# Sheet1.net
KiCad netlist of a schematic drawn in Altium Designer
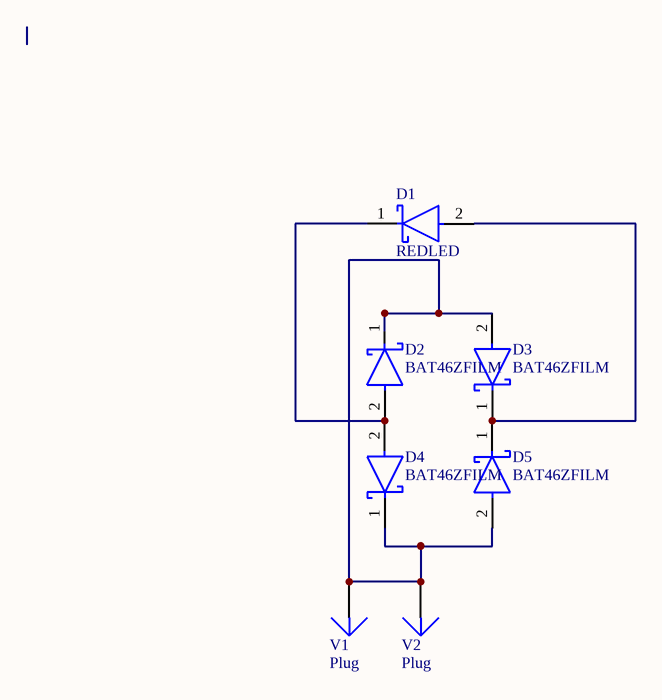
[diagram p0: Sheet1.SchDoc]

(export (version "E")
  (design (tool "Eeschema 10.0.6"))
  (components
    (comp (ref "D1")
      (value "REDLED")
      (footprint "FP-SOD-123-MFG")
      (description "DIODE SCHOTTKY 100V 150MA SOD123")
      (fields
        (field (name "MANUFACTURER") "STMicroelectronics")
        (field (name "MANUFACTURER PART NUMBER") "BAT46ZFILM")
      )
      (libsource (lib "Altium Content Vault") (part "1d6ec82d83fb6aee721767c19dac4b9"))
    )
    (comp (ref "D2")
      (value "BAT46ZFILM")
      (footprint "FP-SOD-123-MFG")
      (description "DIODE SCHOTTKY 100V 150MA SOD123")
      (fields
        (field (name "MANUFACTURER") "STMicroelectronics")
        (field (name "OCTOPART") "https://octopart.com/bat46zfilm-stmicroelectronics-658190")
      )
      (libsource (lib "Altium Content Vault") (part "1d6ec82d83fb6aee721767c19dac4b9"))
    )
    (comp (ref "D3")
      (value "BAT46ZFILM")
      (footprint "FP-SOD-123-MFG")
      (description "DIODE SCHOTTKY 100V 150MA SOD123")
      (fields
        (field (name "MANUFACTURER") "STMicroelectronics")
        (field (name "OCTOPART") "https://octopart.com/bat46zfilm-stmicroelectronics-658190")
      )
      (libsource (lib "Altium Content Vault") (part "1d6ec82d83fb6aee721767c19dac4b9"))
    )
    (comp (ref "D4")
      (value "BAT46ZFILM")
      (footprint "FP-SOD-123-MFG")
      (description "DIODE SCHOTTKY 100V 150MA SOD123")
      (fields
        (field (name "MANUFACTURER") "STMicroelectronics")
        (field (name "OCTOPART") "https://octopart.com/bat46zfilm-stmicroelectronics-658190")
      )
      (libsource (lib "Altium Content Vault") (part "1d6ec82d83fb6aee721767c19dac4b9"))
    )
    (comp (ref "D5")
      (value "BAT46ZFILM")
      (footprint "FP-SOD-123-MFG")
      (description "DIODE SCHOTTKY 100V 150MA SOD123")
      (fields
        (field (name "MANUFACTURER") "STMicroelectronics")
        (field (name "OCTOPART") "https://octopart.com/bat46zfilm-stmicroelectronics-658190")
      )
      (libsource (lib "Altium Content Vault") (part "1d6ec82d83fb6aee721767c19dac4b9"))
    )
    (comp (ref "V1")
      (value "Plug")
      (footprint "PIN1")
      (fields (field (name "PUBLISHER") "Altium Limited"))
      (libsource (lib "Miscellaneous Connectors") (part "Plug"))
    )
    (comp (ref "V2")
      (value "Plug")
      (footprint "PIN1")
      (fields (field (name "PUBLISHER") "Altium Limited"))
      (libsource (lib "Miscellaneous Connectors") (part "Plug"))
    )
  )
  (nets
    (net (code "1") (name "Net-(D1-A)") (class "Default")
      (node (ref "D1") (pin "2") (pinfunction "A_2") (pintype "passive"))
      (node (ref "D3") (pin "1") (pinfunction "C_1") (pintype "passive"))
      (node (ref "D5") (pin "1") (pinfunction "C_1") (pintype "passive"))
    )
    (net (code "2") (name "Net-(D1-C)") (class "Default")
      (node (ref "D1") (pin "1") (pinfunction "C_1") (pintype "passive"))
      (node (ref "D2") (pin "2") (pinfunction "A_2") (pintype "passive"))
      (node (ref "D4") (pin "2") (pinfunction "A_2") (pintype "passive"))
    )
    (net (code "3") (name "Net-(D2-C)") (class "Default")
      (node (ref "D2") (pin "1") (pinfunction "C_1") (pintype "passive"))
      (node (ref "D3") (pin "2") (pinfunction "A_2") (pintype "passive"))
      (node (ref "D4") (pin "1") (pinfunction "C_1") (pintype "passive"))
      (node (ref "D5") (pin "2") (pinfunction "A_2") (pintype "passive"))
      (node (ref "V1") (pin "1") (pinfunction "1_1") (pintype "passive"))
      (node (ref "V2") (pin "1") (pinfunction "1_1") (pintype "passive"))
    )
  )
)
